# Linkable_LED_Matrix_Seperate_RES.net
KiCad netlist of a schematic drawn in EAGLE
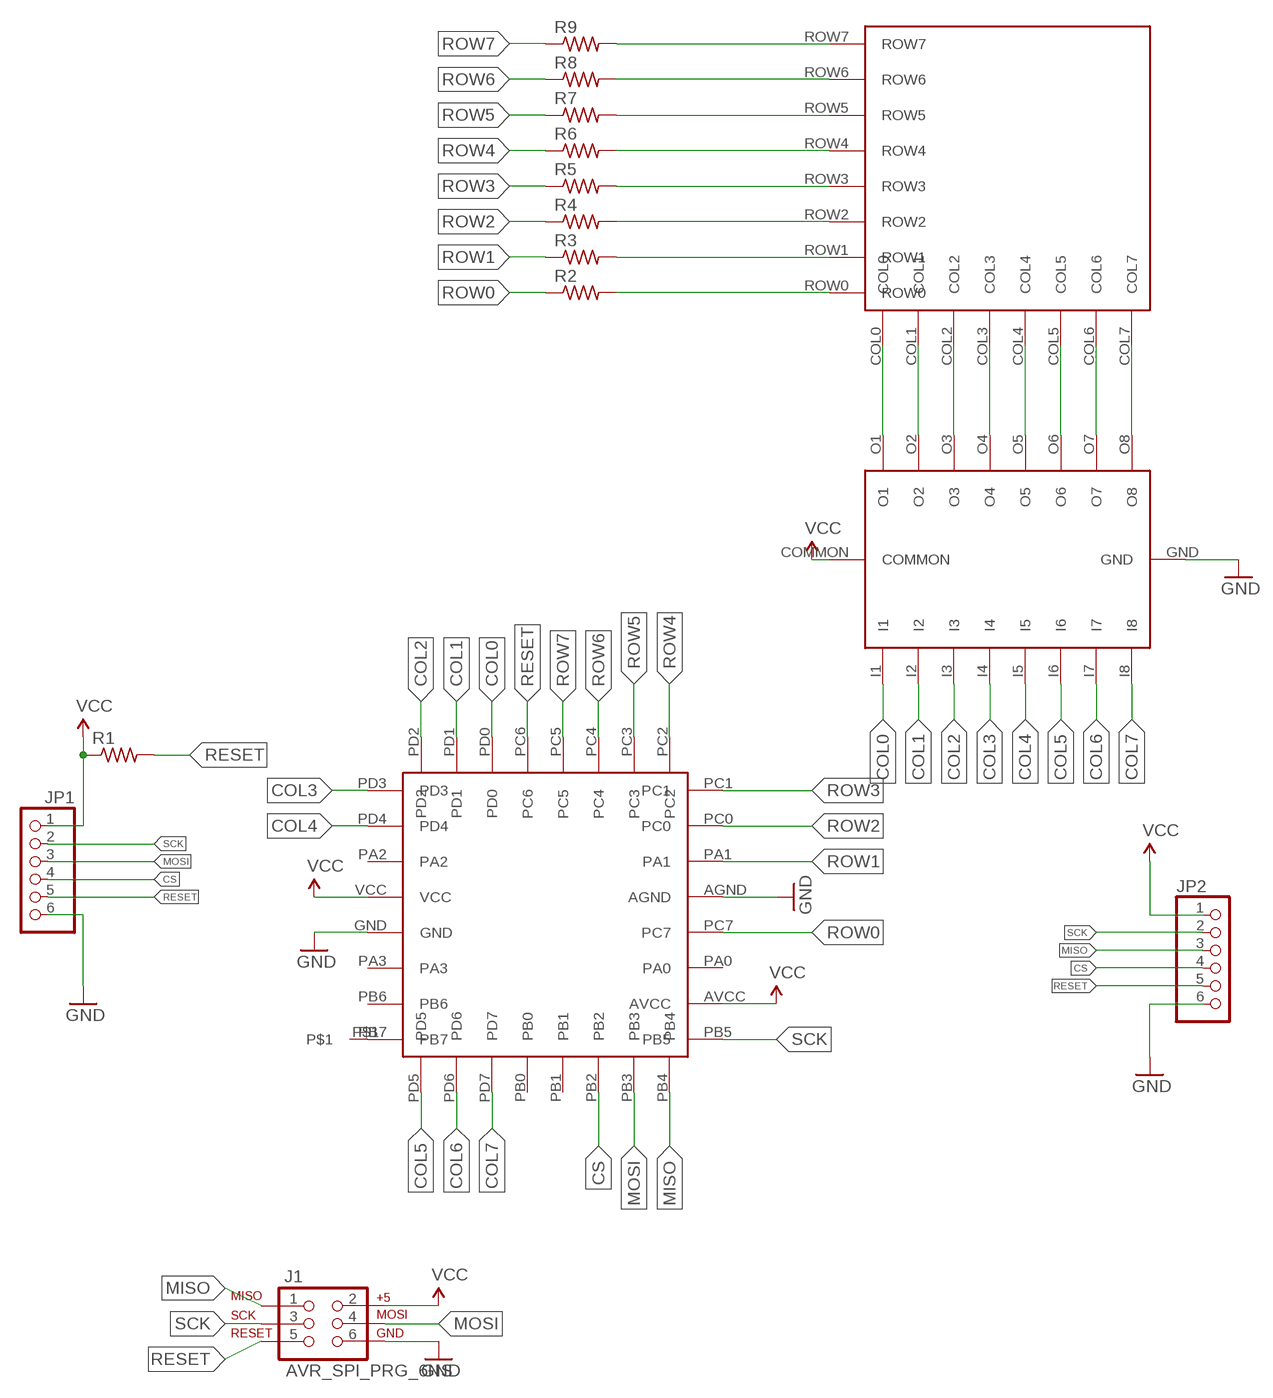
[diagram p0: schematic, sheet 1]

(export (version "E")
  (design (tool "Eeschema 10.0.6"))
  (components
    (comp (ref "J1")
      (value "AVR_SPI_PRG_6NS")
      (footprint "eagle-import:2X3-NS")
      (libsource (lib "eagle-import") (part "AVR_SPI_PRG_6NS"))
    )
    (comp (ref "JP1")
      (value "PINHD-1X6")
      (footprint "eagle-import:1X06")
      (libsource (lib "eagle-import") (part "PINHD-1X6"))
    )
    (comp (ref "JP2")
      (value "PINHD-1X6")
      (footprint "eagle-import:1X06")
      (libsource (lib "eagle-import") (part "PINHD-1X6"))
    )
    (comp (ref "R1")
      (value "R-US_R0603")
      (footprint "eagle-import:R0603")
      (libsource (lib "eagle-import") (part "R-US_R0603"))
    )
    (comp (ref "R2")
      (value "R-US_R0603")
      (footprint "eagle-import:R0603")
      (libsource (lib "eagle-import") (part "R-US_R0603"))
    )
    (comp (ref "R3")
      (value "R-US_R0603")
      (footprint "eagle-import:R0603")
      (libsource (lib "eagle-import") (part "R-US_R0603"))
    )
    (comp (ref "R4")
      (value "R-US_R0603")
      (footprint "eagle-import:R0603")
      (libsource (lib "eagle-import") (part "R-US_R0603"))
    )
    (comp (ref "R5")
      (value "R-US_R0603")
      (footprint "eagle-import:R0603")
      (libsource (lib "eagle-import") (part "R-US_R0603"))
    )
    (comp (ref "R6")
      (value "R-US_R0603")
      (footprint "eagle-import:R0603")
      (libsource (lib "eagle-import") (part "R-US_R0603"))
    )
    (comp (ref "R7")
      (value "R-US_R0603")
      (footprint "eagle-import:R0603")
      (libsource (lib "eagle-import") (part "R-US_R0603"))
    )
    (comp (ref "R8")
      (value "R-US_R0603")
      (footprint "eagle-import:R0603")
      (libsource (lib "eagle-import") (part "R-US_R0603"))
    )
    (comp (ref "R9")
      (value "R-US_R0603")
      (footprint "eagle-import:R0603")
      (libsource (lib "eagle-import") (part "R-US_R0603"))
    )
    (comp (ref "U$1")
      (value "ATTINY48")
      (footprint "eagle-import:ATTINY48")
      (libsource (lib "eagle-import") (part "ATTINY48"))
    )
    (comp (ref "U$2")
      (value "ULN2803AFWG")
      (footprint "eagle-import:ULN2803AFWG")
      (libsource (lib "eagle-import") (part "ULN2803AFWG"))
    )
    (comp (ref "U$3")
      (value "8X8_LED_MATRIX")
      (footprint "eagle-import:8X8_LED_MATRIX")
      (libsource (lib "eagle-import") (part "8X8_LED_MATRIX"))
    )
    (comp (ref "U$4")
      (value "1X1MM_PAD")
      (footprint "eagle-import:1X1MM_PAD")
      (libsource (lib "eagle-import") (part "1X1MM_PAD"))
    )
  )
  (nets
    (net (code "1") (name "COL0") (class "Default")
      (node (ref "U$1") (pin "PD0") (pinfunction "PD0_PD0") (pintype "bidirectional"))
      (node (ref "U$2") (pin "I1") (pinfunction "I1_I1") (pintype "bidirectional"))
    )
    (net (code "2") (name "COL1") (class "Default")
      (node (ref "U$1") (pin "PD1") (pinfunction "PD1_PD1") (pintype "bidirectional"))
      (node (ref "U$2") (pin "I2") (pinfunction "I2_I2") (pintype "bidirectional"))
    )
    (net (code "3") (name "COL2") (class "Default")
      (node (ref "U$1") (pin "PD2") (pinfunction "PD2_PD2") (pintype "bidirectional"))
      (node (ref "U$2") (pin "I3") (pinfunction "I3_I3") (pintype "bidirectional"))
    )
    (net (code "4") (name "COL3") (class "Default")
      (node (ref "U$1") (pin "PD3") (pinfunction "PD3_PD3") (pintype "bidirectional"))
      (node (ref "U$2") (pin "I4") (pinfunction "I4_I4") (pintype "bidirectional"))
    )
    (net (code "5") (name "COL4") (class "Default")
      (node (ref "U$1") (pin "PD4") (pinfunction "PD4_PD4") (pintype "bidirectional"))
      (node (ref "U$2") (pin "I5") (pinfunction "I5_I5") (pintype "bidirectional"))
    )
    (net (code "6") (name "COL5") (class "Default")
      (node (ref "U$1") (pin "PD5") (pinfunction "PD5_PD5") (pintype "bidirectional"))
      (node (ref "U$2") (pin "I6") (pinfunction "I6_I6") (pintype "bidirectional"))
    )
    (net (code "7") (name "COL6") (class "Default")
      (node (ref "U$1") (pin "PD6") (pinfunction "PD6_PD6") (pintype "bidirectional"))
      (node (ref "U$2") (pin "I7") (pinfunction "I7_I7") (pintype "bidirectional"))
    )
    (net (code "8") (name "COL7") (class "Default")
      (node (ref "U$1") (pin "PD7") (pinfunction "PD7_PD7") (pintype "bidirectional"))
      (node (ref "U$2") (pin "I8") (pinfunction "I8_I8") (pintype "bidirectional"))
    )
    (net (code "9") (name "CS") (class "Default")
      (node (ref "JP1") (pin "4") (pinfunction "4_4") (pintype "passive"))
      (node (ref "JP2") (pin "4") (pinfunction "4_4") (pintype "passive"))
      (node (ref "U$1") (pin "PB2") (pinfunction "PB2_PB2") (pintype "bidirectional"))
    )
    (net (code "10") (name "GND") (class "Default")
      (node (ref "J1") (pin "6") (pinfunction "6_6") (pintype "passive"))
      (node (ref "JP1") (pin "6") (pinfunction "6_6") (pintype "passive"))
      (node (ref "JP2") (pin "6") (pinfunction "6_6") (pintype "passive"))
      (node (ref "U$1") (pin "AGND") (pinfunction "AGND_AGND") (pintype "bidirectional"))
      (node (ref "U$1") (pin "GND") (pinfunction "GND_GND") (pintype "bidirectional"))
      (node (ref "U$2") (pin "GND") (pinfunction "GND_GND") (pintype "bidirectional"))
    )
    (net (code "11") (name "MISO") (class "Default")
      (node (ref "J1") (pin "1") (pinfunction "1_1") (pintype "passive"))
      (node (ref "JP2") (pin "3") (pinfunction "3_3") (pintype "passive"))
      (node (ref "U$1") (pin "PB4") (pinfunction "PB4_PB4") (pintype "bidirectional"))
    )
    (net (code "12") (name "MOSI") (class "Default")
      (node (ref "J1") (pin "4") (pinfunction "4_4") (pintype "passive"))
      (node (ref "JP1") (pin "3") (pinfunction "3_3") (pintype "passive"))
      (node (ref "U$1") (pin "PB3") (pinfunction "PB3_PB3") (pintype "bidirectional"))
    )
    (net (code "13") (name "Net-(R2-Pad2)") (class "Default")
      (node (ref "R2") (pin "2") (pinfunction "2_2") (pintype "passive"))
      (node (ref "U$3") (pin "ROW0") (pinfunction "ROW0_ROW0") (pintype "bidirectional"))
    )
    (net (code "14") (name "Net-(R3-Pad2)") (class "Default")
      (node (ref "R3") (pin "2") (pinfunction "2_2") (pintype "passive"))
      (node (ref "U$3") (pin "ROW1") (pinfunction "ROW1_ROW1") (pintype "bidirectional"))
    )
    (net (code "15") (name "Net-(R4-Pad2)") (class "Default")
      (node (ref "R4") (pin "2") (pinfunction "2_2") (pintype "passive"))
      (node (ref "U$3") (pin "ROW2") (pinfunction "ROW2_ROW2") (pintype "bidirectional"))
    )
    (net (code "16") (name "Net-(R5-Pad2)") (class "Default")
      (node (ref "R5") (pin "2") (pinfunction "2_2") (pintype "passive"))
      (node (ref "U$3") (pin "ROW3") (pinfunction "ROW3_ROW3") (pintype "bidirectional"))
    )
    (net (code "17") (name "Net-(R6-Pad2)") (class "Default")
      (node (ref "R6") (pin "2") (pinfunction "2_2") (pintype "passive"))
      (node (ref "U$3") (pin "ROW4") (pinfunction "ROW4_ROW4") (pintype "bidirectional"))
    )
    (net (code "18") (name "Net-(R7-Pad2)") (class "Default")
      (node (ref "R7") (pin "2") (pinfunction "2_2") (pintype "passive"))
      (node (ref "U$3") (pin "ROW5") (pinfunction "ROW5_ROW5") (pintype "bidirectional"))
    )
    (net (code "19") (name "Net-(R8-Pad2)") (class "Default")
      (node (ref "R8") (pin "2") (pinfunction "2_2") (pintype "passive"))
      (node (ref "U$3") (pin "ROW6") (pinfunction "ROW6_ROW6") (pintype "bidirectional"))
    )
    (net (code "20") (name "Net-(R9-Pad2)") (class "Default")
      (node (ref "R9") (pin "2") (pinfunction "2_2") (pintype "passive"))
      (node (ref "U$3") (pin "ROW7") (pinfunction "ROW7_ROW7") (pintype "bidirectional"))
    )
    (net (code "21") (name "Net-(U$1-PadPB7)") (class "Default")
      (node (ref "U$1") (pin "PB7") (pinfunction "PB7_PB7") (pintype "bidirectional"))
      (node (ref "U$4") (pin "P$1") (pinfunction "P$1_P$1") (pintype "bidirectional"))
    )
    (net (code "22") (name "Net-(U$2-PadO1)") (class "Default")
      (node (ref "U$2") (pin "O1") (pinfunction "O1_O1") (pintype "bidirectional"))
      (node (ref "U$3") (pin "COL0") (pinfunction "COL0_COL0") (pintype "bidirectional"))
    )
    (net (code "23") (name "Net-(U$2-PadO2)") (class "Default")
      (node (ref "U$2") (pin "O2") (pinfunction "O2_O2") (pintype "bidirectional"))
      (node (ref "U$3") (pin "COL1") (pinfunction "COL1_COL1") (pintype "bidirectional"))
    )
    (net (code "24") (name "Net-(U$2-PadO3)") (class "Default")
      (node (ref "U$2") (pin "O3") (pinfunction "O3_O3") (pintype "bidirectional"))
      (node (ref "U$3") (pin "COL2") (pinfunction "COL2_COL2") (pintype "bidirectional"))
    )
    (net (code "25") (name "Net-(U$2-PadO4)") (class "Default")
      (node (ref "U$2") (pin "O4") (pinfunction "O4_O4") (pintype "bidirectional"))
      (node (ref "U$3") (pin "COL3") (pinfunction "COL3_COL3") (pintype "bidirectional"))
    )
    (net (code "26") (name "Net-(U$2-PadO5)") (class "Default")
      (node (ref "U$2") (pin "O5") (pinfunction "O5_O5") (pintype "bidirectional"))
      (node (ref "U$3") (pin "COL4") (pinfunction "COL4_COL4") (pintype "bidirectional"))
    )
    (net (code "27") (name "Net-(U$2-PadO6)") (class "Default")
      (node (ref "U$2") (pin "O6") (pinfunction "O6_O6") (pintype "bidirectional"))
      (node (ref "U$3") (pin "COL5") (pinfunction "COL5_COL5") (pintype "bidirectional"))
    )
    (net (code "28") (name "Net-(U$2-PadO7)") (class "Default")
      (node (ref "U$2") (pin "O7") (pinfunction "O7_O7") (pintype "bidirectional"))
      (node (ref "U$3") (pin "COL6") (pinfunction "COL6_COL6") (pintype "bidirectional"))
    )
    (net (code "29") (name "Net-(U$2-PadO8)") (class "Default")
      (node (ref "U$2") (pin "O8") (pinfunction "O8_O8") (pintype "bidirectional"))
      (node (ref "U$3") (pin "COL7") (pinfunction "COL7_COL7") (pintype "bidirectional"))
    )
    (net (code "30") (name "RESET") (class "Default")
      (node (ref "J1") (pin "5") (pinfunction "5_5") (pintype "passive"))
      (node (ref "JP1") (pin "5") (pinfunction "5_5") (pintype "passive"))
      (node (ref "JP2") (pin "5") (pinfunction "5_5") (pintype "passive"))
      (node (ref "R1") (pin "2") (pinfunction "2_2") (pintype "passive"))
      (node (ref "U$1") (pin "PC6") (pinfunction "PC6_PC6") (pintype "bidirectional"))
    )
    (net (code "31") (name "ROW0") (class "Default")
      (node (ref "R2") (pin "1") (pinfunction "1_1") (pintype "passive"))
      (node (ref "U$1") (pin "PC7") (pinfunction "PC7_PC7") (pintype "bidirectional"))
    )
    (net (code "32") (name "ROW1") (class "Default")
      (node (ref "R3") (pin "1") (pinfunction "1_1") (pintype "passive"))
      (node (ref "U$1") (pin "PA1") (pinfunction "PA1_PA1") (pintype "bidirectional"))
    )
    (net (code "33") (name "ROW2") (class "Default")
      (node (ref "R4") (pin "1") (pinfunction "1_1") (pintype "passive"))
      (node (ref "U$1") (pin "PC0") (pinfunction "PC0_PC0") (pintype "bidirectional"))
    )
    (net (code "34") (name "ROW3") (class "Default")
      (node (ref "R5") (pin "1") (pinfunction "1_1") (pintype "passive"))
      (node (ref "U$1") (pin "PC1") (pinfunction "PC1_PC1") (pintype "bidirectional"))
    )
    (net (code "35") (name "ROW4") (class "Default")
      (node (ref "R6") (pin "1") (pinfunction "1_1") (pintype "passive"))
      (node (ref "U$1") (pin "PC2") (pinfunction "PC2_PC2") (pintype "bidirectional"))
    )
    (net (code "36") (name "ROW5") (class "Default")
      (node (ref "R7") (pin "1") (pinfunction "1_1") (pintype "passive"))
      (node (ref "U$1") (pin "PC3") (pinfunction "PC3_PC3") (pintype "bidirectional"))
    )
    (net (code "37") (name "ROW6") (class "Default")
      (node (ref "R8") (pin "1") (pinfunction "1_1") (pintype "passive"))
      (node (ref "U$1") (pin "PC4") (pinfunction "PC4_PC4") (pintype "bidirectional"))
    )
    (net (code "38") (name "ROW7") (class "Default")
      (node (ref "R9") (pin "1") (pinfunction "1_1") (pintype "passive"))
      (node (ref "U$1") (pin "PC5") (pinfunction "PC5_PC5") (pintype "bidirectional"))
    )
    (net (code "39") (name "SCK") (class "Default")
      (node (ref "J1") (pin "3") (pinfunction "3_3") (pintype "passive"))
      (node (ref "JP1") (pin "2") (pinfunction "2_2") (pintype "passive"))
      (node (ref "JP2") (pin "2") (pinfunction "2_2") (pintype "passive"))
      (node (ref "U$1") (pin "PB5") (pinfunction "PB5_PB5") (pintype "bidirectional"))
    )
    (net (code "40") (name "VCC") (class "Default")
      (node (ref "J1") (pin "2") (pinfunction "2_2") (pintype "passive"))
      (node (ref "JP1") (pin "1") (pinfunction "1_1") (pintype "passive"))
      (node (ref "JP2") (pin "1") (pinfunction "1_1") (pintype "passive"))
      (node (ref "R1") (pin "1") (pinfunction "1_1") (pintype "passive"))
      (node (ref "U$1") (pin "AVCC") (pinfunction "AVCC_AVCC") (pintype "bidirectional"))
      (node (ref "U$1") (pin "VCC") (pinfunction "VCC_VCC") (pintype "bidirectional"))
      (node (ref "U$2") (pin "COMMON") (pinfunction "COMMON_COMMON") (pintype "bidirectional"))
    )
    (net (code "41") (name "unconnected-(U$1-PadPA0)") (class "Default")
      (node (ref "U$1") (pin "PA0") (pinfunction "PA0_PA0") (pintype "bidirectional"))
    )
    (net (code "42") (name "unconnected-(U$1-PadPA2)") (class "Default")
      (node (ref "U$1") (pin "PA2") (pinfunction "PA2_PA2") (pintype "bidirectional"))
    )
    (net (code "43") (name "unconnected-(U$1-PadPA3)") (class "Default")
      (node (ref "U$1") (pin "PA3") (pinfunction "PA3_PA3") (pintype "bidirectional"))
    )
    (net (code "44") (name "unconnected-(U$1-PadPB0)") (class "Default")
      (node (ref "U$1") (pin "PB0") (pinfunction "PB0_PB0") (pintype "bidirectional"))
    )
    (net (code "45") (name "unconnected-(U$1-PadPB1)") (class "Default")
      (node (ref "U$1") (pin "PB1") (pinfunction "PB1_PB1") (pintype "bidirectional"))
    )
    (net (code "46") (name "unconnected-(U$1-PadPB6)") (class "Default")
      (node (ref "U$1") (pin "PB6") (pinfunction "PB6_PB6") (pintype "bidirectional"))
    )
  )
)
